# FMC_HPC1.net
KiCad netlist of a schematic drawn in Altium Designer
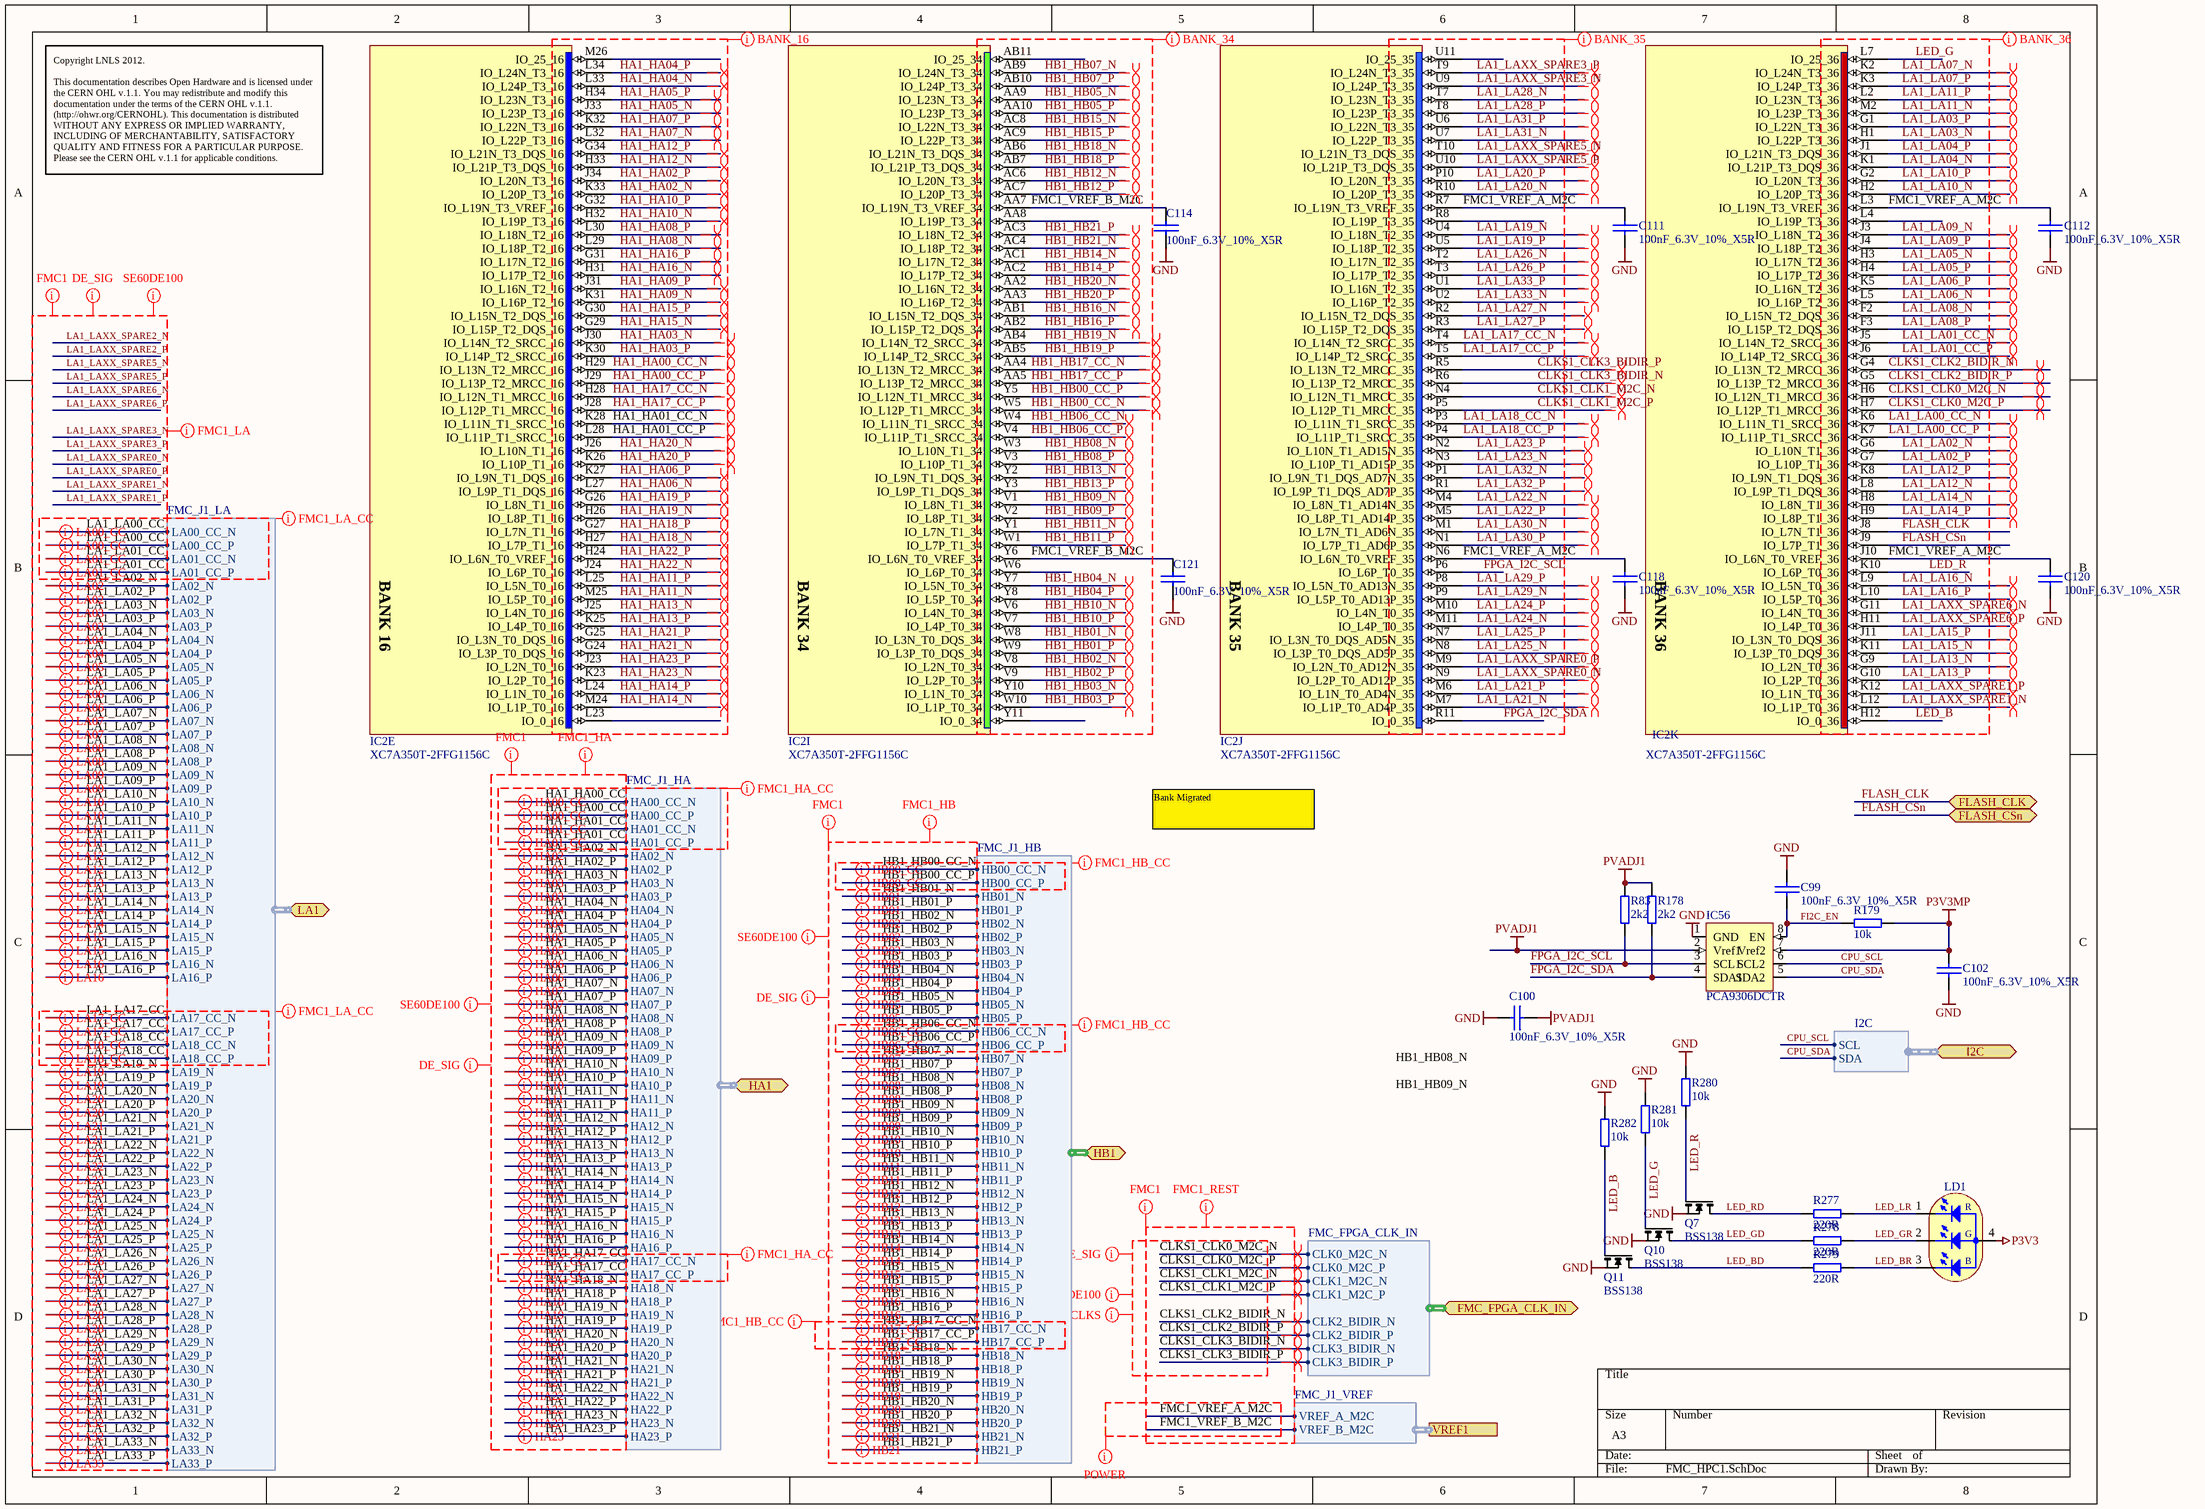
[diagram p0: FMC_HPC1.SchDoc]

(export (version "E")
  (design (tool "Eeschema 10.0.6"))
  (components
    (comp (ref "C99")
      (value "100nF_6.3V_10%_X5R")
      (footprint "0201C")
      (description "Capacitor SMD")
      (libsource (lib "LIBRARY_SCH") (part "CAP_SMD_0201"))
    )
    (comp (ref "C100")
      (value "100nF_6.3V_10%_X5R")
      (footprint "0201C")
      (description "Capacitor SMD")
      (libsource (lib "LIBRARY_SCH") (part "CAP_SMD_0201"))
    )
    (comp (ref "C102")
      (value "100nF_6.3V_10%_X5R")
      (footprint "0201C")
      (description "Capacitor SMD")
      (libsource (lib "LIBRARY_SCH") (part "CAP_SMD_0201"))
    )
    (comp (ref "C111")
      (value "100nF_6.3V_10%_X5R")
      (footprint "0201C")
      (description "Capacitor SMD")
      (libsource (lib "LIBRARY_SCH") (part "CAP_SMD_0201"))
    )
    (comp (ref "C112")
      (value "100nF_6.3V_10%_X5R")
      (footprint "0201C")
      (description "Capacitor SMD")
      (libsource (lib "LIBRARY_SCH") (part "CAP_SMD_0201"))
    )
    (comp (ref "C114")
      (value "100nF_6.3V_10%_X5R")
      (footprint "0201C")
      (description "Capacitor SMD")
      (libsource (lib "LIBRARY_SCH") (part "CAP_SMD_0201"))
    )
    (comp (ref "C118")
      (value "100nF_6.3V_10%_X5R")
      (footprint "0201C")
      (description "Capacitor SMD")
      (libsource (lib "LIBRARY_SCH") (part "CAP_SMD_0201"))
    )
    (comp (ref "C120")
      (value "100nF_6.3V_10%_X5R")
      (footprint "0201C")
      (description "Capacitor SMD")
      (libsource (lib "LIBRARY_SCH") (part "CAP_SMD_0201"))
    )
    (comp (ref "C121")
      (value "100nF_6.3V_10%_X5R")
      (footprint "0201C")
      (description "Capacitor SMD")
      (libsource (lib "LIBRARY_SCH") (part "CAP_SMD_0201"))
    )
    (comp (ref "IC2")
      (value "XC7A350T-2FFG1156C")
      (footprint "BGA1156C100P34X34_3500X3500X335")
      (description "Artix-6 FPGA, 16 GTPs, 600 User I/Os, 1156-Pin BGA, Speed Grade 2, Commercial Grade, Pb-Free")
      (fields (field (name "MANUFACTURER") "XILINX") (field (name "AUTHOR") "CERN DEM JLC"))
      (libsource (lib "AMC_FMC_Carrier") (part "XC7A350T-2FFG1156C"))
    )
    (comp (ref "IC56")
      (value "PCA9306DCTR")
      (footprint "SSOP8")
      (description "I2C BUS VOLTAGE-LEVEL TRANSLATOR")
      (libsource (lib "LIBRARY_SCH") (part "IFC_PCA9306"))
    )
    (comp (ref "LD1")
      (value "Red/Green/Blue")
      (footprint "LED_OPTEK_OVSRRGBCC3_a")
      (description "Right Angle Tricolor (RGB) Surface Mount LED, Body 3.2x1mm")
      (fields
        (field (name "PART NUMBER") "LED_OPTEK_OVSRRGBCC3_a")
        (field (name "MANUFACTURER") "OPTEK / TT ELECTRONICS")
        (field (name "AUTHOR") "CERN DEM JLC")
      )
      (libsource (lib "ICs And Semiconductors") (part "LED_OPTEK_OVSRRGBCC3"))
    )
    (comp (ref "Q7") (value "BSS138") (footprint "SOT-23") (libsource (lib "LIBRARY_SCH") (part "Q_BSS138")))
    (comp (ref "Q10") (value "BSS138") (footprint "SOT-23") (libsource (lib "LIBRARY_SCH") (part "Q_BSS138")))
    (comp (ref "Q11") (value "BSS138") (footprint "SOT-23") (libsource (lib "LIBRARY_SCH") (part "Q_BSS138")))
    (comp (ref "R83")
      (value "2k2")
      (footprint "0402R")
      (description "SMD Resistor")
      (libsource (lib "LIBRARY_SCH") (part "RES_0402"))
    )
    (comp (ref "R178")
      (value "2k2")
      (footprint "0402R")
      (description "SMD Resistor")
      (libsource (lib "LIBRARY_SCH") (part "RES_0402"))
    )
    (comp (ref "R179")
      (value "10k")
      (footprint "0402R")
      (description "SMD Resistor")
      (libsource (lib "LIBRARY_SCH") (part "RES_0402"))
    )
    (comp (ref "R277")
      (value "220R")
      (footprint "0402R")
      (description "SMD Resistor")
      (libsource (lib "LIBRARY_SCH") (part "RES_0402"))
    )
    (comp (ref "R278")
      (value "220R")
      (footprint "0402R")
      (description "SMD Resistor")
      (libsource (lib "LIBRARY_SCH") (part "RES_0402"))
    )
    (comp (ref "R279")
      (value "220R")
      (footprint "0402R")
      (description "SMD Resistor")
      (libsource (lib "LIBRARY_SCH") (part "RES_0402"))
    )
    (comp (ref "R280")
      (value "10k")
      (footprint "0402R")
      (description "SMD Resistor")
      (libsource (lib "LIBRARY_SCH") (part "RES_0402"))
    )
    (comp (ref "R281")
      (value "10k")
      (footprint "0402R")
      (description "SMD Resistor")
      (libsource (lib "LIBRARY_SCH") (part "RES_0402"))
    )
    (comp (ref "R282")
      (value "10k")
      (footprint "0402R")
      (description "SMD Resistor")
      (libsource (lib "LIBRARY_SCH") (part "RES_0402"))
    )
  )
  (nets
    (net (code "7") (name "/CLKS1_CLK0_M2C_N") (class "Default")
      (node (ref "IC2") (pin "H6") (pinfunction "IO_L12N_T1_MRCC_36_H6") (pintype "bidirectional"))
    )
    (net (code "8") (name "/CLKS1_CLK0_M2C_P") (class "Default")
      (node (ref "IC2") (pin "H7") (pinfunction "IO_L12P_T1_MRCC_36_H7") (pintype "bidirectional"))
    )
    (net (code "9") (name "/CLKS1_CLK1_M2C_N") (class "Default")
      (node (ref "IC2") (pin "N4") (pinfunction "IO_L12N_T1_MRCC_35_N4") (pintype "bidirectional"))
    )
    (net (code "10") (name "/CLKS1_CLK1_M2C_P") (class "Default")
      (node (ref "IC2") (pin "P5") (pinfunction "IO_L12P_T1_MRCC_35_P5") (pintype "bidirectional"))
    )
    (net (code "11") (name "/CLKS1_CLK2_BIDIR_N") (class "Default")
      (node (ref "IC2") (pin "G4") (pinfunction "IO_L13N_T2_MRCC_36_G4") (pintype "bidirectional"))
    )
    (net (code "12") (name "/CLKS1_CLK2_BIDIR_P") (class "Default")
      (node (ref "IC2") (pin "G5") (pinfunction "IO_L13P_T2_MRCC_36_G5") (pintype "bidirectional"))
    )
    (net (code "13") (name "/CLKS1_CLK3_BIDIR_N") (class "Default")
      (node (ref "IC2") (pin "R6") (pinfunction "IO_L13P_T2_MRCC_35_R6") (pintype "bidirectional"))
    )
    (net (code "14") (name "/CLKS1_CLK3_BIDIR_P") (class "Default")
      (node (ref "IC2") (pin "R5") (pinfunction "IO_L13N_T2_MRCC_35_R5") (pintype "bidirectional"))
    )
    (net (code "15") (name "/CPU_SCL") (class "Default")
      (node (ref "IC56") (pin "6") (pinfunction "SCL2_6") (pintype "bidirectional"))
    )
    (net (code "16") (name "/CPU_SDA") (class "Default")
      (node (ref "IC56") (pin "5") (pinfunction "SDA2_5") (pintype "bidirectional"))
    )
    (net (code "17") (name "/FI2C_EN") (class "Default")
      (node (ref "C99") (pin "1") (pinfunction "1_1") (pintype "passive"))
      (node (ref "IC56") (pin "8") (pinfunction "EN_8") (pintype "input"))
      (node (ref "R179") (pin "1") (pinfunction "1_1") (pintype "passive"))
    )
    (net (code "18") (name "/FLASH_CLK") (class "Default")
      (node (ref "IC2") (pin "J8") (pinfunction "IO_L7N_T1_36_J8") (pintype "bidirectional"))
    )
    (net (code "19") (name "/FLASH_CSn") (class "Default")
      (node (ref "IC2") (pin "J9") (pinfunction "IO_L7P_T1_36_J9") (pintype "bidirectional"))
    )
    (net (code "20") (name "/FMC1_VREF_A_M2C") (class "Default")
      (node (ref "C111") (pin "1") (pinfunction "1_1") (pintype "passive"))
      (node (ref "C112") (pin "1") (pinfunction "1_1") (pintype "passive"))
      (node (ref "C118") (pin "1") (pinfunction "1_1") (pintype "passive"))
      (node (ref "C120") (pin "1") (pinfunction "1_1") (pintype "passive"))
      (node (ref "IC2") (pin "J10") (pinfunction "IO_L6N_T0_VREF_36_J10") (pintype "bidirectional"))
      (node (ref "IC2") (pin "L3") (pinfunction "IO_L19N_T3_VREF_36_L3") (pintype "bidirectional"))
      (node (ref "IC2") (pin "N6") (pinfunction "IO_L6N_T0_VREF_35_N6") (pintype "bidirectional"))
      (node (ref "IC2") (pin "R7") (pinfunction "IO_L19N_T3_VREF_35_R7") (pintype "bidirectional"))
    )
    (net (code "21") (name "/FMC1_VREF_B_M2C") (class "Default")
      (node (ref "C114") (pin "1") (pinfunction "1_1") (pintype "passive"))
      (node (ref "C121") (pin "1") (pinfunction "1_1") (pintype "passive"))
      (node (ref "IC2") (pin "AA7") (pinfunction "IO_L19N_T3_VREF_34_AA7") (pintype "bidirectional"))
      (node (ref "IC2") (pin "Y6") (pinfunction "IO_L6N_T0_VREF_34_Y6") (pintype "bidirectional"))
    )
    (net (code "22") (name "/FPGA_I2C_SCL") (class "Default")
      (node (ref "IC2") (pin "P6") (pinfunction "IO_L6P_T0_35_P6") (pintype "bidirectional"))
      (node (ref "IC56") (pin "3") (pinfunction "SCL1_3") (pintype "bidirectional"))
      (node (ref "R83") (pin "1") (pinfunction "1_1") (pintype "passive"))
    )
    (net (code "23") (name "/FPGA_I2C_SDA") (class "Default")
      (node (ref "IC2") (pin "R11") (pinfunction "IO_0_35_R11") (pintype "bidirectional"))
      (node (ref "IC56") (pin "4") (pinfunction "SDA1_4") (pintype "bidirectional"))
      (node (ref "R178") (pin "1") (pinfunction "1_1") (pintype "passive"))
    )
    (net (code "24") (name "/HA1_HA00_CC_N") (class "Default")
      (node (ref "IC2") (pin "H29") (pinfunction "IO_L13N_T2_MRCC_16_H29") (pintype "bidirectional"))
    )
    (net (code "25") (name "/HA1_HA00_CC_P") (class "Default")
      (node (ref "IC2") (pin "J29") (pinfunction "IO_L13P_T2_MRCC_16_J29") (pintype "bidirectional"))
    )
    (net (code "26") (name "/HA1_HA01_CC_N") (class "Default")
      (node (ref "IC2") (pin "K28") (pinfunction "IO_L11N_T1_SRCC_16_K28") (pintype "bidirectional"))
    )
    (net (code "27") (name "/HA1_HA01_CC_P") (class "Default")
      (node (ref "IC2") (pin "L28") (pinfunction "IO_L11P_T1_SRCC_16_L28") (pintype "bidirectional"))
    )
    (net (code "28") (name "/HA1_HA02_N") (class "Default")
      (node (ref "IC2") (pin "K33") (pinfunction "IO_L20P_T3_16_K33") (pintype "bidirectional"))
    )
    (net (code "29") (name "/HA1_HA02_P") (class "Default")
      (node (ref "IC2") (pin "J34") (pinfunction "IO_L20N_T3_16_J34") (pintype "bidirectional"))
    )
    (net (code "30") (name "/HA1_HA03_N") (class "Default")
      (node (ref "IC2") (pin "J30") (pinfunction "IO_L14N_T2_SRCC_16_J30") (pintype "bidirectional"))
    )
    (net (code "31") (name "/HA1_HA03_P") (class "Default")
      (node (ref "IC2") (pin "K30") (pinfunction "IO_L14P_T2_SRCC_16_K30") (pintype "bidirectional"))
    )
    (net (code "32") (name "/HA1_HA04_N") (class "Default")
      (node (ref "IC2") (pin "L33") (pinfunction "IO_L24P_T3_16_L33") (pintype "bidirectional"))
    )
    (net (code "33") (name "/HA1_HA04_P") (class "Default")
      (node (ref "IC2") (pin "L34") (pinfunction "IO_L24N_T3_16_L34") (pintype "bidirectional"))
    )
    (net (code "34") (name "/HA1_HA05_N") (class "Default")
      (node (ref "IC2") (pin "J33") (pinfunction "IO_L23P_T3_16_J33") (pintype "bidirectional"))
    )
    (net (code "35") (name "/HA1_HA05_P") (class "Default")
      (node (ref "IC2") (pin "H34") (pinfunction "IO_L23N_T3_16_H34") (pintype "bidirectional"))
    )
    (net (code "36") (name "/HA1_HA06_N") (class "Default")
      (node (ref "IC2") (pin "L27") (pinfunction "IO_L9P_T1_DQS_16_L27") (pintype "bidirectional"))
    )
    (net (code "37") (name "/HA1_HA06_P") (class "Default")
      (node (ref "IC2") (pin "K27") (pinfunction "IO_L9N_T1_DQS_16_K27") (pintype "bidirectional"))
    )
    (net (code "38") (name "/HA1_HA07_N") (class "Default")
      (node (ref "IC2") (pin "L32") (pinfunction "IO_L22P_T3_16_L32") (pintype "bidirectional"))
    )
    (net (code "39") (name "/HA1_HA07_P") (class "Default")
      (node (ref "IC2") (pin "K32") (pinfunction "IO_L22N_T3_16_K32") (pintype "bidirectional"))
    )
    (net (code "40") (name "/HA1_HA08_N") (class "Default")
      (node (ref "IC2") (pin "L29") (pinfunction "IO_L18P_T2_16_L29") (pintype "bidirectional"))
    )
    (net (code "41") (name "/HA1_HA08_P") (class "Default")
      (node (ref "IC2") (pin "L30") (pinfunction "IO_L18N_T2_16_L30") (pintype "bidirectional"))
    )
    (net (code "42") (name "/HA1_HA09_N") (class "Default")
      (node (ref "IC2") (pin "K31") (pinfunction "IO_L16P_T2_16_K31") (pintype "bidirectional"))
    )
    (net (code "43") (name "/HA1_HA09_P") (class "Default")
      (node (ref "IC2") (pin "J31") (pinfunction "IO_L16N_T2_16_J31") (pintype "bidirectional"))
    )
    (net (code "44") (name "/HA1_HA10_N") (class "Default")
      (node (ref "IC2") (pin "H32") (pinfunction "IO_L19P_T3_16_H32") (pintype "bidirectional"))
    )
    (net (code "45") (name "/HA1_HA10_P") (class "Default")
      (node (ref "IC2") (pin "G32") (pinfunction "IO_L19N_T3_VREF_16_G32") (pintype "bidirectional"))
    )
    (net (code "46") (name "/HA1_HA11_N") (class "Default")
      (node (ref "IC2") (pin "M25") (pinfunction "IO_L5P_T0_16_M25") (pintype "bidirectional"))
    )
    (net (code "47") (name "/HA1_HA11_P") (class "Default")
      (node (ref "IC2") (pin "L25") (pinfunction "IO_L5N_T0_16_L25") (pintype "bidirectional"))
    )
    (net (code "48") (name "/HA1_HA12_N") (class "Default")
      (node (ref "IC2") (pin "H33") (pinfunction "IO_L21P_T3_DQS_16_H33") (pintype "bidirectional"))
    )
    (net (code "49") (name "/HA1_HA12_P") (class "Default")
      (node (ref "IC2") (pin "G34") (pinfunction "IO_L21N_T3_DQS_16_G34") (pintype "bidirectional"))
    )
    (net (code "50") (name "/HA1_HA13_N") (class "Default")
      (node (ref "IC2") (pin "J25") (pinfunction "IO_L4N_T0_16_J25") (pintype "bidirectional"))
    )
    (net (code "51") (name "/HA1_HA13_P") (class "Default")
      (node (ref "IC2") (pin "K25") (pinfunction "IO_L4P_T0_16_K25") (pintype "bidirectional"))
    )
    (net (code "52") (name "/HA1_HA14_N") (class "Default")
      (node (ref "IC2") (pin "M24") (pinfunction "IO_L1P_T0_16_M24") (pintype "bidirectional"))
    )
    (net (code "53") (name "/HA1_HA14_P") (class "Default")
      (node (ref "IC2") (pin "L24") (pinfunction "IO_L1N_T0_16_L24") (pintype "bidirectional"))
    )
    (net (code "54") (name "/HA1_HA15_N") (class "Default")
      (node (ref "IC2") (pin "G29") (pinfunction "IO_L15P_T2_DQS_16_G29") (pintype "bidirectional"))
    )
    (net (code "55") (name "/HA1_HA15_P") (class "Default")
      (node (ref "IC2") (pin "G30") (pinfunction "IO_L15N_T2_DQS_16_G30") (pintype "bidirectional"))
    )
    (net (code "56") (name "/HA1_HA16_N") (class "Default")
      (node (ref "IC2") (pin "H31") (pinfunction "IO_L17P_T2_16_H31") (pintype "bidirectional"))
    )
    (net (code "57") (name "/HA1_HA16_P") (class "Default")
      (node (ref "IC2") (pin "G31") (pinfunction "IO_L17N_T2_16_G31") (pintype "bidirectional"))
    )
    (net (code "58") (name "/HA1_HA17_CC_N") (class "Default")
      (node (ref "IC2") (pin "H28") (pinfunction "IO_L12N_T1_MRCC_16_H28") (pintype "bidirectional"))
    )
    (net (code "59") (name "/HA1_HA17_CC_P") (class "Default")
      (node (ref "IC2") (pin "J28") (pinfunction "IO_L12P_T1_MRCC_16_J28") (pintype "bidirectional"))
    )
    (net (code "60") (name "/HA1_HA18_N") (class "Default")
      (node (ref "IC2") (pin "H27") (pinfunction "IO_L7P_T1_16_H27") (pintype "bidirectional"))
    )
    (net (code "61") (name "/HA1_HA18_P") (class "Default")
      (node (ref "IC2") (pin "G27") (pinfunction "IO_L7N_T1_16_G27") (pintype "bidirectional"))
    )
    (net (code "62") (name "/HA1_HA19_N") (class "Default")
      (node (ref "IC2") (pin "H26") (pinfunction "IO_L8P_T1_16_H26") (pintype "bidirectional"))
    )
    (net (code "63") (name "/HA1_HA19_P") (class "Default")
      (node (ref "IC2") (pin "G26") (pinfunction "IO_L8N_T1_16_G26") (pintype "bidirectional"))
    )
    (net (code "64") (name "/HA1_HA20_N") (class "Default")
      (node (ref "IC2") (pin "J26") (pinfunction "IO_L10N_T1_16_J26") (pintype "bidirectional"))
    )
    (net (code "65") (name "/HA1_HA20_P") (class "Default")
      (node (ref "IC2") (pin "K26") (pinfunction "IO_L10P_T1_16_K26") (pintype "bidirectional"))
    )
    (net (code "66") (name "/HA1_HA21_N") (class "Default")
      (node (ref "IC2") (pin "G24") (pinfunction "IO_L3P_T0_DQS_16_G24") (pintype "bidirectional"))
    )
    (net (code "67") (name "/HA1_HA21_P") (class "Default")
      (node (ref "IC2") (pin "G25") (pinfunction "IO_L3N_T0_DQS_16_G25") (pintype "bidirectional"))
    )
    (net (code "68") (name "/HA1_HA22_N") (class "Default")
      (node (ref "IC2") (pin "J24") (pinfunction "IO_L6P_T0_16_J24") (pintype "bidirectional"))
    )
    (net (code "69") (name "/HA1_HA22_P") (class "Default")
      (node (ref "IC2") (pin "H24") (pinfunction "IO_L6N_T0_VREF_16_H24") (pintype "bidirectional"))
    )
    (net (code "70") (name "/HA1_HA23_N") (class "Default")
      (node (ref "IC2") (pin "K23") (pinfunction "IO_L2P_T0_16_K23") (pintype "bidirectional"))
    )
    (net (code "71") (name "/HA1_HA23_P") (class "Default")
      (node (ref "IC2") (pin "J23") (pinfunction "IO_L2N_T0_16_J23") (pintype "bidirectional"))
    )
    (net (code "72") (name "/HB1_HB00_CC_N") (class "Default")
      (node (ref "IC2") (pin "W5") (pinfunction "IO_L12P_T1_MRCC_34_W5") (pintype "bidirectional"))
    )
    (net (code "73") (name "/HB1_HB00_CC_P") (class "Default")
      (node (ref "IC2") (pin "Y5") (pinfunction "IO_L12N_T1_MRCC_34_Y5") (pintype "bidirectional"))
    )
    (net (code "74") (name "/HB1_HB01_N") (class "Default")
      (node (ref "IC2") (pin "W8") (pinfunction "IO_L3N_T0_DQS_34_W8") (pintype "bidirectional"))
    )
    (net (code "75") (name "/HB1_HB01_P") (class "Default")
      (node (ref "IC2") (pin "W9") (pinfunction "IO_L3P_T0_DQS_34_W9") (pintype "bidirectional"))
    )
    (net (code "76") (name "/HB1_HB02_N") (class "Default")
      (node (ref "IC2") (pin "V8") (pinfunction "IO_L2N_T0_34_V8") (pintype "bidirectional"))
    )
    (net (code "77") (name "/HB1_HB02_P") (class "Default")
      (node (ref "IC2") (pin "V9") (pinfunction "IO_L2P_T0_34_V9") (pintype "bidirectional"))
    )
    (net (code "78") (name "/HB1_HB03_N") (class "Default")
      (node (ref "IC2") (pin "Y10") (pinfunction "IO_L1N_T0_34_Y10") (pintype "bidirectional"))
    )
    (net (code "79") (name "/HB1_HB03_P") (class "Default")
      (node (ref "IC2") (pin "W10") (pinfunction "IO_L1P_T0_34_W10") (pintype "bidirectional"))
    )
    (net (code "80") (name "/HB1_HB04_N") (class "Default")
      (node (ref "IC2") (pin "Y7") (pinfunction "IO_L5N_T0_34_Y7") (pintype "bidirectional"))
    )
    (net (code "81") (name "/HB1_HB04_P") (class "Default")
      (node (ref "IC2") (pin "Y8") (pinfunction "IO_L5P_T0_34_Y8") (pintype "bidirectional"))
    )
    (net (code "82") (name "/HB1_HB05_N") (class "Default")
      (node (ref "IC2") (pin "AA9") (pinfunction "IO_L23N_T3_34_AA9") (pintype "bidirectional"))
    )
    (net (code "83") (name "/HB1_HB05_P") (class "Default")
      (node (ref "IC2") (pin "AA10") (pinfunction "IO_L23P_T3_34_AA10") (pintype "bidirectional"))
    )
    (net (code "84") (name "/HB1_HB06_CC_N") (class "Default")
      (node (ref "IC2") (pin "W4") (pinfunction "IO_L11N_T1_SRCC_34_W4") (pintype "bidirectional"))
    )
    (net (code "85") (name "/HB1_HB06_CC_P") (class "Default")
      (node (ref "IC2") (pin "V4") (pinfunction "IO_L11P_T1_SRCC_34_V4") (pintype "bidirectional"))
    )
    (net (code "86") (name "/HB1_HB07_N") (class "Default")
      (node (ref "IC2") (pin "AB9") (pinfunction "IO_L24N_T3_34_AB9") (pintype "bidirectional"))
    )
    (net (code "87") (name "/HB1_HB07_P") (class "Default")
      (node (ref "IC2") (pin "AB10") (pinfunction "IO_L24P_T3_34_AB10") (pintype "bidirectional"))
    )
    (net (code "88") (name "/HB1_HB08_N") (class "Default")
      (node (ref "IC2") (pin "W3") (pinfunction "IO_L10N_T1_34_W3") (pintype "bidirectional"))
    )
    (net (code "89") (name "/HB1_HB08_P") (class "Default")
      (node (ref "IC2") (pin "V3") (pinfunction "IO_L10P_T1_34_V3") (pintype "bidirectional"))
    )
    (net (code "90") (name "/HB1_HB09_N") (class "Default")
      (node (ref "IC2") (pin "V1") (pinfunction "IO_L8N_T1_34_V1") (pintype "bidirectional"))
    )
    (net (code "91") (name "/HB1_HB09_P") (class "Default")
      (node (ref "IC2") (pin "V2") (pinfunction "IO_L8P_T1_34_V2") (pintype "bidirectional"))
    )
    (net (code "92") (name "/HB1_HB10_N") (class "Default")
      (node (ref "IC2") (pin "V6") (pinfunction "IO_L4N_T0_34_V6") (pintype "bidirectional"))
    )
    (net (code "93") (name "/HB1_HB10_P") (class "Default")
      (node (ref "IC2") (pin "V7") (pinfunction "IO_L4P_T0_34_V7") (pintype "bidirectional"))
    )
    (net (code "94") (name "/HB1_HB11_N") (class "Default")
      (node (ref "IC2") (pin "Y1") (pinfunction "IO_L7N_T1_34_Y1") (pintype "bidirectional"))
    )
    (net (code "95") (name "/HB1_HB11_P") (class "Default")
      (node (ref "IC2") (pin "W1") (pinfunction "IO_L7P_T1_34_W1") (pintype "bidirectional"))
    )
    (net (code "96") (name "/HB1_HB12_N") (class "Default")
      (node (ref "IC2") (pin "AC6") (pinfunction "IO_L20N_T3_34_AC6") (pintype "bidirectional"))
    )
    (net (code "97") (name "/HB1_HB12_P") (class "Default")
      (node (ref "IC2") (pin "AC7") (pinfunction "IO_L20P_T3_34_AC7") (pintype "bidirectional"))
    )
    (net (code "98") (name "/HB1_HB13_N") (class "Default")
      (node (ref "IC2") (pin "Y2") (pinfunction "IO_L9N_T1_DQS_34_Y2") (pintype "bidirectional"))
    )
    (net (code "99") (name "/HB1_HB13_P") (class "Default")
      (node (ref "IC2") (pin "Y3") (pinfunction "IO_L9P_T1_DQS_34_Y3") (pintype "bidirectional"))
    )
    (net (code "100") (name "/HB1_HB14_N") (class "Default")
      (node (ref "IC2") (pin "AC1") (pinfunction "IO_L17N_T2_34_AC1") (pintype "bidirectional"))
    )
    (net (code "101") (name "/HB1_HB14_P") (class "Default")
      (node (ref "IC2") (pin "AC2") (pinfunction "IO_L17P_T2_34_AC2") (pintype "bidirectional"))
    )
    (net (code "102") (name "/HB1_HB15_N") (class "Default")
      (node (ref "IC2") (pin "AC8") (pinfunction "IO_L22N_T3_34_AC8") (pintype "bidirectional"))
    )
    (net (code "103") (name "/HB1_HB15_P") (class "Default")
      (node (ref "IC2") (pin "AC9") (pinfunction "IO_L22P_T3_34_AC9") (pintype "bidirectional"))
    )
    (net (code "104") (name "/HB1_HB16_N") (class "Default")
      (node (ref "IC2") (pin "AB1") (pinfunction "IO_L15N_T2_DQS_34_AB1") (pintype "bidirectional"))
    )
    (net (code "105") (name "/HB1_HB16_P") (class "Default")
      (node (ref "IC2") (pin "AB2") (pinfunction "IO_L15P_T2_DQS_34_AB2") (pintype "bidirectional"))
    )
    (net (code "106") (name "/HB1_HB17_CC_N") (class "Default")
      (node (ref "IC2") (pin "AA4") (pinfunction "IO_L13N_T2_MRCC_34_AA4") (pintype "bidirectional"))
    )
    (net (code "107") (name "/HB1_HB17_CC_P") (class "Default")
      (node (ref "IC2") (pin "AA5") (pinfunction "IO_L13P_T2_MRCC_34_AA5") (pintype "bidirectional"))
    )
    (net (code "108") (name "/HB1_HB18_N") (class "Default")
      (node (ref "IC2") (pin "AB6") (pinfunction "IO_L21N_T3_DQS_34_AB6") (pintype "bidirectional"))
    )
    (net (code "109") (name "/HB1_HB18_P") (class "Default")
      (node (ref "IC2") (pin "AB7") (pinfunction "IO_L21P_T3_DQS_34_AB7") (pintype "bidirectional"))
    )
    (net (code "110") (name "/HB1_HB19_N") (class "Default")
      (node (ref "IC2") (pin "AB4") (pinfunction "IO_L14N_T2_SRCC_34_AB4") (pintype "bidirectional"))
    )
    (net (code "111") (name "/HB1_HB19_P") (class "Default")
      (node (ref "IC2") (pin "AB5") (pinfunction "IO_L14P_T2_SRCC_34_AB5") (pintype "bidirectional"))
    )
    (net (code "112") (name "/HB1_HB20_N") (class "Default")
      (node (ref "IC2") (pin "AA2") (pinfunction "IO_L16N_T2_34_AA2") (pintype "bidirectional"))
    )
    (net (code "113") (name "/HB1_HB20_P") (class "Default")
      (node (ref "IC2") (pin "AA3") (pinfunction "IO_L16P_T2_34_AA3") (pintype "bidirectional"))
    )
    (net (code "114") (name "/HB1_HB21_N") (class "Default")
      (node (ref "IC2") (pin "AC4") (pinfunction "IO_L18P_T2_34_AC4") (pintype "bidirectional"))
    )
    (net (code "115") (name "/HB1_HB21_P") (class "Default")
      (node (ref "IC2") (pin "AC3") (pinfunction "IO_L18N_T2_34_AC3") (pintype "bidirectional"))
    )
    (net (code "116") (name "/LA1_LA00_CC_N") (class "Default")
      (node (ref "IC2") (pin "K6") (pinfunction "IO_L11N_T1_SRCC_36_K6") (pintype "bidirectional"))
    )
    (net (code "117") (name "/LA1_LA00_CC_P") (class "Default")
      (node (ref "IC2") (pin "K7") (pinfunction "IO_L11P_T1_SRCC_36_K7") (pintype "bidirectional"))
    )
    (net (code "118") (name "/LA1_LA01_CC_N") (class "Default")
      (node (ref "IC2") (pin "J5") (pinfunction "IO_L14N_T2_SRCC_36_J5") (pintype "bidirectional"))
    )
    (net (code "119") (name "/LA1_LA01_CC_P") (class "Default")
      (node (ref "IC2") (pin "J6") (pinfunction "IO_L14P_T2_SRCC_36_J6") (pintype "bidirectional"))
    )
    (net (code "120") (name "/LA1_LA02_N") (class "Default")
      (node (ref "IC2") (pin "G6") (pinfunction "IO_L10N_T1_36_G6") (pintype "bidirectional"))
    )
    (net (code "121") (name "/LA1_LA02_P") (class "Default")
      (node (ref "IC2") (pin "G7") (pinfunction "IO_L10P_T1_36_G7") (pintype "bidirectional"))
    )
    (net (code "122") (name "/LA1_LA03_N") (class "Default")
      (node (ref "IC2") (pin "H1") (pinfunction "IO_L22P_T3_36_H1") (pintype "bidirectional"))
    )
    (net (code "123") (name "/LA1_LA03_P") (class "Default")
      (node (ref "IC2") (pin "G1") (pinfunction "IO_L22N_T3_36_G1") (pintype "bidirectional"))
    )
    (net (code "124") (name "/LA1_LA04_N") (class "Default")
      (node (ref "IC2") (pin "K1") (pinfunction "IO_L21P_T3_DQS_36_K1") (pintype "bidirectional"))
    )
    (net (code "125") (name "/LA1_LA04_P") (class "Default")
      (node (ref "IC2") (pin "J1") (pinfunction "IO_L21N_T3_DQS_36_J1") (pintype "bidirectional"))
    )
    (net (code "126") (name "/LA1_LA05_N") (class "Default")
      (node (ref "IC2") (pin "H3") (pinfunction "IO_L17N_T2_36_H3") (pintype "bidirectional"))
    )
    (net (code "127") (name "/LA1_LA05_P") (class "Default")
      (node (ref "IC2") (pin "H4") (pinfunction "IO_L17P_T2_36_H4") (pintype "bidirectional"))
    )
    (net (code "128") (name "/LA1_LA06_N") (class "Default")
      (node (ref "IC2") (pin "L5") (pinfunction "IO_L16P_T2_36_L5") (pintype "bidirectional"))
    )
    (net (code "129") (name "/LA1_LA06_P") (class "Default")
      (node (ref "IC2") (pin "K5") (pinfunction "IO_L16N_T2_36_K5") (pintype "bidirectional"))
    )
    (net (code "130") (name "/LA1_LA07_N") (class "Default")
      (node (ref "IC2") (pin "K2") (pinfunction "IO_L24N_T3_36_K2") (pintype "bidirectional"))
    )
    (net (code "131") (name "/LA1_LA07_P") (class "Default")
      (node (ref "IC2") (pin "K3") (pinfunction "IO_L24P_T3_36_K3") (pintype "bidirectional"))
    )
    (net (code "132") (name "/LA1_LA08_N") (class "Default")
      (node (ref "IC2") (pin "F2") (pinfunction "IO_L15N_T2_DQS_36_F2") (pintype "bidirectional"))
    )
    (net (code "133") (name "/LA1_LA08_P") (class "Default")
      (node (ref "IC2") (pin "F3") (pinfunction "IO_L15P_T2_DQS_36_F3") (pintype "bidirectional"))
    )
    (net (code "134") (name "/LA1_LA09_N") (class "Default")
      (node (ref "IC2") (pin "J3") (pinfunction "IO_L18N_T2_36_J3") (pintype "bidirectional"))
    )
    (net (code "135") (name "/LA1_LA09_P") (class "Default")
      (node (ref "IC2") (pin "J4") (pinfunction "IO_L18P_T2_36_J4") (pintype "bidirectional"))
    )
    (net (code "136") (name "/LA1_LA10_N") (class "Default")
      (node (ref "IC2") (pin "H2") (pinfunction "IO_L20P_T3_36_H2") (pintype "bidirectional"))
    )
    (net (code "137") (name "/LA1_LA10_P") (class "Default")
      (node (ref "IC2") (pin "G2") (pinfunction "IO_L20N_T3_36_G2") (pintype "bidirectional"))
    )
    (net (code "138") (name "/LA1_LA11_N") (class "Default")
      (node (ref "IC2") (pin "M2") (pinfunction "IO_L23P_T3_36_M2") (pintype "bidirectional"))
    )
    (net (code "139") (name "/LA1_LA11_P") (class "Default")
      (node (ref "IC2") (pin "L2") (pinfunction "IO_L23N_T3_36_L2") (pintype "bidirectional"))
    )
    (net (code "140") (name "/LA1_LA12_N") (class "Default")
      (node (ref "IC2") (pin "L8") (pinfunction "IO_L9P_T1_DQS_36_L8") (pintype "bidirectional"))
    )
    (net (code "141") (name "/LA1_LA12_P") (class "Default")
      (node (ref "IC2") (pin "K8") (pinfunction "IO_L9N_T1_DQS_36_K8") (pintype "bidirectional"))
    )
    (net (code "142") (name "/LA1_LA13_N") (class "Default")
      (node (ref "IC2") (pin "G9") (pinfunction "IO_L2N_T0_36_G9") (pintype "bidirectional"))
    )
    (net (code "143") (name "/LA1_LA13_P") (class "Default")
      (node (ref "IC2") (pin "G10") (pinfunction "IO_L2P_T0_36_G10") (pintype "bidirectional"))
    )
    (net (code "144") (name "/LA1_LA14_N") (class "Default")
      (node (ref "IC2") (pin "H8") (pinfunction "IO_L8N_T1_36_H8") (pintype "bidirectional"))
    )
    (net (code "145") (name "/LA1_LA14_P") (class "Default")
      (node (ref "IC2") (pin "H9") (pinfunction "IO_L8P_T1_36_H9") (pintype "bidirectional"))
    )
    (net (code "146") (name "/LA1_LA15_N") (class "Default")
      (node (ref "IC2") (pin "K11") (pinfunction "IO_L3P_T0_DQS_36_K11") (pintype "bidirectional"))
    )
    (net (code "147") (name "/LA1_LA15_P") (class "Default")
      (node (ref "IC2") (pin "J11") (pinfunction "IO_L3N_T0_DQS_36_J11") (pintype "bidirectional"))
    )
    (net (code "148") (name "/LA1_LA16_N") (class "Default")
      (node (ref "IC2") (pin "L9") (pinfunction "IO_L5N_T0_36_L9") (pintype "bidirectional"))
    )
    (net (code "149") (name "/LA1_LA16_P") (class "Default")
      (node (ref "IC2") (pin "L10") (pinfunction "IO_L5P_T0_36_L10") (pintype "bidirectional"))
    )
    (net (code "150") (name "/LA1_LA17_CC_N") (class "Default")
      (node (ref "IC2") (pin "T4") (pinfunction "IO_L14N_T2_SRCC_35_T4") (pintype "bidirectional"))
    )
    (net (code "151") (name "/LA1_LA17_CC_P") (class "Default")
      (node (ref "IC2") (pin "T5") (pinfunction "IO_L14P_T2_SRCC_35_T5") (pintype "bidirectional"))
    )
    (net (code "152") (name "/LA1_LA18_CC_N") (class "Default")
      (node (ref "IC2") (pin "P3") (pinfunction "IO_L11N_T1_SRCC_35_P3") (pintype "bidirectional"))
    )
    (net (code "153") (name "/LA1_LA18_CC_P") (class "Default")
      (node (ref "IC2") (pin "P4") (pinfunction "IO_L11P_T1_SRCC_35_P4") (pintype "bidirectional"))
    )
    (net (code "154") (name "/LA1_LA19_N") (class "Default")
      (node (ref "IC2") (pin "U4") (pinfunction "IO_L18N_T2_35_U4") (pintype "bidirectional"))
    )
    (net (code "155") (name "/LA1_LA19_P") (class "Default")
      (node (ref "IC2") (pin "U5") (pinfunction "IO_L18P_T2_35_U5") (pintype "bidirectional"))
    )
    (net (code "156") (name "/LA1_LA20_N") (class "Default")
      (node (ref "IC2") (pin "R10") (pinfunction "IO_L20P_T3_35_R10") (pintype "bidirectional"))
    )
    (net (code "157") (name "/LA1_LA20_P") (class "Default")
      (node (ref "IC2") (pin "P10") (pinfunction "IO_L20N_T3_35_P10") (pintype "bidirectional"))
    )
    (net (code "158") (name "/LA1_LA21_N") (class "Default")
      (node (ref "IC2") (pin "M7") (pinfunction "IO_L1P_T0_AD4P_35_M7") (pintype "bidirectional"))
    )
    (net (code "159") (name "/LA1_LA21_P") (class "Default")
      (node (ref "IC2") (pin "M6") (pinfunction "IO_L1N_T0_AD4N_35_M6") (pintype "bidirectional"))
    )
    (net (code "160") (name "/LA1_LA22_N") (class "Default")
      (node (ref "IC2") (pin "M4") (pinfunction "IO_L8N_T1_AD14N_35_M4") (pintype "bidirectional"))
    )
    (net (code "161") (name "/LA1_LA22_P") (class "Default")
      (node (ref "IC2") (pin "M5") (pinfunction "IO_L8P_T1_AD14P_35_M5") (pintype "bidirectional"))
    )
    (net (code "162") (name "/LA1_LA23_N") (class "Default")
      (node (ref "IC2") (pin "N3") (pinfunction "IO_L10P_T1_AD15P_35_N3") (pintype "bidirectional"))
    )
    (net (code "163") (name "/LA1_LA23_P") (class "Default")
      (node (ref "IC2") (pin "N2") (pinfunction "IO_L10N_T1_AD15N_35_N2") (pintype "bidirectional"))
    )
    (net (code "164") (name "/LA1_LA24_N") (class "Default")
      (node (ref "IC2") (pin "M11") (pinfunction "IO_L4P_T0_35_M11") (pintype "bidirectional"))
    )
    (net (code "165") (name "/LA1_LA24_P") (class "Default")
      (node (ref "IC2") (pin "M10") (pinfunction "IO_L4N_T0_35_M10") (pintype "bidirectional"))
    )
    (net (code "166") (name "/LA1_LA25_N") (class "Default")
      (node (ref "IC2") (pin "N8") (pinfunction "IO_L3P_T0_DQS_AD5P_35_N8") (pintype "bidirectional"))
    )
    (net (code "167") (name "/LA1_LA25_P") (class "Default")
      (node (ref "IC2") (pin "N7") (pinfunction "IO_L3N_T0_DQS_AD5N_35_N7") (pintype "bidirectional"))
    )
    (net (code "168") (name "/LA1_LA26_N") (class "Default")
      (node (ref "IC2") (pin "T2") (pinfunction "IO_L17N_T2_35_T2") (pintype "bidirectional"))
    )
    (net (code "169") (name "/LA1_LA26_P") (class "Default")
      (node (ref "IC2") (pin "T3") (pinfunction "IO_L17P_T2_35_T3") (pintype "bidirectional"))
    )
    (net (code "170") (name "/LA1_LA27_N") (class "Default")
      (node (ref "IC2") (pin "R2") (pinfunction "IO_L15N_T2_DQS_35_R2") (pintype "bidirectional"))
    )
    (net (code "171") (name "/LA1_LA27_P") (class "Default")
      (node (ref "IC2") (pin "R3") (pinfunction "IO_L15P_T2_DQS_35_R3") (pintype "bidirectional"))
    )
    (net (code "172") (name "/LA1_LA28_N") (class "Default")
      (node (ref "IC2") (pin "T7") (pinfunction "IO_L23N_T3_35_T7") (pintype "bidirectional"))
    )
    (net (code "173") (name "/LA1_LA28_P") (class "Default")
      (node (ref "IC2") (pin "T8") (pinfunction "IO_L23P_T3_35_T8") (pintype "bidirectional"))
    )
    (net (code "174") (name "/LA1_LA29_N") (class "Default")
      (node (ref "IC2") (pin "P9") (pinfunction "IO_L5P_T0_AD13P_35_P9") (pintype "bidirectional"))
    )
    (net (code "175") (name "/LA1_LA29_P") (class "Default")
      (node (ref "IC2") (pin "P8") (pinfunction "IO_L5N_T0_AD13N_35_P8") (pintype "bidirectional"))
    )
    (net (code "176") (name "/LA1_LA30_N") (class "Default")
      (node (ref "IC2") (pin "M1") (pinfunction "IO_L7N_T1_AD6N_35_M1") (pintype "bidirectional"))
    )
    (net (code "177") (name "/LA1_LA30_P") (class "Default")
      (node (ref "IC2") (pin "N1") (pinfunction "IO_L7P_T1_AD6P_35_N1") (pintype "bidirectional"))
    )
    (net (code "178") (name "/LA1_LA31_N") (class "Default")
      (node (ref "IC2") (pin "U7") (pinfunction "IO_L22P_T3_35_U7") (pintype "bidirectional"))
    )
    (net (code "179") (name "/LA1_LA31_P") (class "Default")
      (node (ref "IC2") (pin "U6") (pinfunction "IO_L22N_T3_35_U6") (pintype "bidirectional"))
    )
    (net (code "180") (name "/LA1_LA32_N") (class "Default")
      (node (ref "IC2") (pin "P1") (pinfunction "IO_L9N_T1_DQS_AD7N_35_P1") (pintype "bidirectional"))
    )
    (net (code "181") (name "/LA1_LA32_P") (class "Default")
      (node (ref "IC2") (pin "R1") (pinfunction "IO_L9P_T1_DQS_AD7P_35_R1") (pintype "bidirectional"))
    )
    (net (code "182") (name "/LA1_LA33_N") (class "Default")
      (node (ref "IC2") (pin "U2") (pinfunction "IO_L16P_T2_35_U2") (pintype "bidirectional"))
    )
    (net (code "183") (name "/LA1_LA33_P") (class "Default")
      (node (ref "IC2") (pin "U1") (pinfunction "IO_L16N_T2_35_U1") (pintype "bidirectional"))
    )
    (net (code "184") (name "/LA1_LAXX_SPARE0_N") (class "Default")
      (node (ref "IC2") (pin "N9") (pinfunction "IO_L2P_T0_AD12P_35_N9") (pintype "bidirectional"))
    )
    (net (code "185") (name "/LA1_LAXX_SPARE0_P") (class "Default")
      (node (ref "IC2") (pin "M9") (pinfunction "IO_L2N_T0_AD12N_35_M9") (pintype "bidirectional"))
    )
    (net (code "186") (name "/LA1_LAXX_SPARE1_N") (class "Default")
      (node (ref "IC2") (pin "L12") (pinfunction "IO_L1P_T0_36_L12") (pintype "bidirectional"))
    )
    (net (code "187") (name "/LA1_LAXX_SPARE1_P") (class "Default")
      (node (ref "IC2") (pin "K12") (pinfunction "IO_L1N_T0_36_K12") (pintype "bidirectional"))
    )
    (net (code "190") (name "/LA1_LAXX_SPARE3_N") (class "Default")
      (node (ref "IC2") (pin "U9") (pinfunction "IO_L24P_T3_35_U9") (pintype "bidirectional"))
    )
    (net (code "191") (name "/LA1_LAXX_SPARE3_P") (class "Default")
      (node (ref "IC2") (pin "T9") (pinfunction "IO_L24N_T3_35_T9") (pintype "bidirectional"))
    )
    (net (code "192") (name "/LA1_LAXX_SPARE5_N") (class "Default")
      (node (ref "IC2") (pin "T10") (pinfunction "IO_L21N_T3_DQS_35_T10") (pintype "bidirectional"))
    )
    (net (code "193") (name "/LA1_LAXX_SPARE5_P") (class "Default")
      (node (ref "IC2") (pin "U10") (pinfunction "IO_L21P_T3_DQS_35_U10") (pintype "bidirectional"))
    )
    (net (code "194") (name "/LA1_LAXX_SPARE6_N") (class "Default")
      (node (ref "IC2") (pin "G11") (pinfunction "IO_L4N_T0_36_G11") (pintype "bidirectional"))
    )
    (net (code "195") (name "/LA1_LAXX_SPARE6_P") (class "Default")
      (node (ref "IC2") (pin "H11") (pinfunction "IO_L4P_T0_36_H11") (pintype "bidirectional"))
    )
    (net (code "196") (name "/LED_B") (class "Default")
      (node (ref "IC2") (pin "H12") (pinfunction "IO_0_36_H12") (pintype "bidirectional"))
      (node (ref "Q11") (pin "1") (pinfunction "G_1") (pintype "input"))
      (node (ref "R282") (pin "2") (pinfunction "2_2") (pintype "passive"))
    )
    (net (code "197") (name "/LED_BD") (class "Default")
      (node (ref "Q11") (pin "3") (pinfunction "D_3") (pintype "passive"))
      (node (ref "R279") (pin "1") (pinfunction "1_1") (pintype "passive"))
    )
    (net (code "198") (name "/LED_BR") (class "Default")
      (node (ref "LD1") (pin "3") (pinfunction "AB_3") (pintype "passive"))
      (node (ref "R279") (pin "2") (pinfunction "2_2") (pintype "passive"))
    )
    (net (code "199") (name "/LED_G") (class "Default")
      (node (ref "IC2") (pin "L7") (pinfunction "IO_25_36_L7") (pintype "bidirectional"))
      (node (ref "Q10") (pin "1") (pinfunction "G_1") (pintype "input"))
      (node (ref "R281") (pin "2") (pinfunction "2_2") (pintype "passive"))
    )
    (net (code "200") (name "/LED_GD") (class "Default")
      (node (ref "Q10") (pin "3") (pinfunction "D_3") (pintype "passive"))
      (node (ref "R278") (pin "1") (pinfunction "1_1") (pintype "passive"))
    )
    (net (code "201") (name "/LED_GR") (class "Default")
      (node (ref "LD1") (pin "2") (pinfunction "AG_2") (pintype "passive"))
      (node (ref "R278") (pin "2") (pinfunction "2_2") (pintype "passive"))
    )
    (net (code "202") (name "/LED_LR") (class "Default")
      (node (ref "LD1") (pin "1") (pinfunction "AR_1") (pintype "passive"))
      (node (ref "R277") (pin "2") (pinfunction "2_2") (pintype "passive"))
    )
    (net (code "203") (name "/LED_R") (class "Default")
      (node (ref "IC2") (pin "K10") (pinfunction "IO_L6P_T0_36_K10") (pintype "bidirectional"))
      (node (ref "Q7") (pin "1") (pinfunction "G_1") (pintype "input"))
      (node (ref "R280") (pin "2") (pinfunction "2_2") (pintype "passive"))
    )
    (net (code "204") (name "/LED_RD") (class "Default")
      (node (ref "Q7") (pin "3") (pinfunction "D_3") (pintype "passive"))
      (node (ref "R277") (pin "1") (pinfunction "1_1") (pintype "passive"))
    )
    (net (code "211") (name "GND") (class "Default")
      (node (ref "C100") (pin "2") (pinfunction "2_2") (pintype "passive"))
      (node (ref "C102") (pin "2") (pinfunction "2_2") (pintype "passive"))
      (node (ref "C111") (pin "2") (pinfunction "2_2") (pintype "passive"))
      (node (ref "C112") (pin "2") (pinfunction "2_2") (pintype "passive"))
      (node (ref "C114") (pin "2") (pinfunction "2_2") (pintype "passive"))
      (node (ref "C118") (pin "2") (pinfunction "2_2") (pintype "passive"))
      (node (ref "C120") (pin "2") (pinfunction "2_2") (pintype "passive"))
      (node (ref "C121") (pin "2") (pinfunction "2_2") (pintype "passive"))
      (node (ref "C99") (pin "2") (pinfunction "2_2") (pintype "passive"))
      (node (ref "IC56") (pin "1") (pinfunction "GND_1") (pintype "power_in"))
      (node (ref "Q10") (pin "2") (pinfunction "S_2") (pintype "passive"))
      (node (ref "Q11") (pin "2") (pinfunction "S_2") (pintype "passive"))
      (node (ref "Q7") (pin "2") (pinfunction "S_2") (pintype "passive"))
      (node (ref "R280") (pin "1") (pinfunction "1_1") (pintype "passive"))
      (node (ref "R281") (pin "1") (pinfunction "1_1") (pintype "passive"))
      (node (ref "R282") (pin "1") (pinfunction "1_1") (pintype "passive"))
    )
    (net (code "212") (name "P3V3") (class "Default")
      (node (ref "LD1") (pin "4") (pinfunction "CC_4") (pintype "passive"))
    )
    (net (code "213") (name "P3V3MP") (class "Default")
      (node (ref "C102") (pin "1") (pinfunction "1_1") (pintype "passive"))
      (node (ref "IC56") (pin "7") (pinfunction "Vref2_7") (pintype "input"))
      (node (ref "R179") (pin "2") (pinfunction "2_2") (pintype "passive"))
    )
    (net (code "214") (name "PVADJ1") (class "Default")
      (node (ref "C100") (pin "1") (pinfunction "1_1") (pintype "passive"))
      (node (ref "IC56") (pin "2") (pinfunction "Vref1_2") (pintype "input"))
      (node (ref "R178") (pin "2") (pinfunction "2_2") (pintype "passive"))
      (node (ref "R83") (pin "2") (pinfunction "2_2") (pintype "passive"))
    )
    (net (code "215") (name "unconnected-(IC2E-IO_0_16-PadL23)") (class "Default")
      (node (ref "IC2") (pin "L23") (pinfunction "IO_0_16_L23") (pintype "bidirectional"))
    )
    (net (code "216") (name "unconnected-(IC2E-IO_25_16-PadM26)") (class "Default")
      (node (ref "IC2") (pin "M26") (pinfunction "IO_25_16_M26") (pintype "bidirectional"))
    )
    (net (code "217") (name "unconnected-(IC2I-IO_0_34-PadY11)") (class "Default")
      (node (ref "IC2") (pin "Y11") (pinfunction "IO_0_34_Y11") (pintype "bidirectional"))
    )
    (net (code "218") (name "unconnected-(IC2I-IO_25_34-PadAB11)") (class "Default")
      (node (ref "IC2") (pin "AB11") (pinfunction "IO_25_34_AB11") (pintype "bidirectional"))
    )
    (net (code "219") (name "unconnected-(IC2I-IO_L6P_T0_34-PadW6)") (class "Default")
      (node (ref "IC2") (pin "W6") (pinfunction "IO_L6P_T0_34_W6") (pintype "bidirectional"))
    )
    (net (code "220") (name "unconnected-(IC2I-IO_L19P_T3_34-PadAA8)") (class "Default")
      (node (ref "IC2") (pin "AA8") (pinfunction "IO_L19P_T3_34_AA8") (pintype "bidirectional"))
    )
    (net (code "221") (name "unconnected-(IC2J-IO_25_35-PadU11)") (class "Default")
      (node (ref "IC2") (pin "U11") (pinfunction "IO_25_35_U11") (pintype "bidirectional"))
    )
    (net (code "222") (name "unconnected-(IC2J-IO_L19P_T3_35-PadR8)") (class "Default")
      (node (ref "IC2") (pin "R8") (pinfunction "IO_L19P_T3_35_R8") (pintype "bidirectional"))
    )
    (net (code "223") (name "unconnected-(IC2K-IO_L19P_T3_36-PadL4)") (class "Default")
      (node (ref "IC2") (pin "L4") (pinfunction "IO_L19P_T3_36_L4") (pintype "bidirectional"))
    )
  )
)
